# Sheet1.net
KiCad netlist of a schematic drawn in Altium Designer
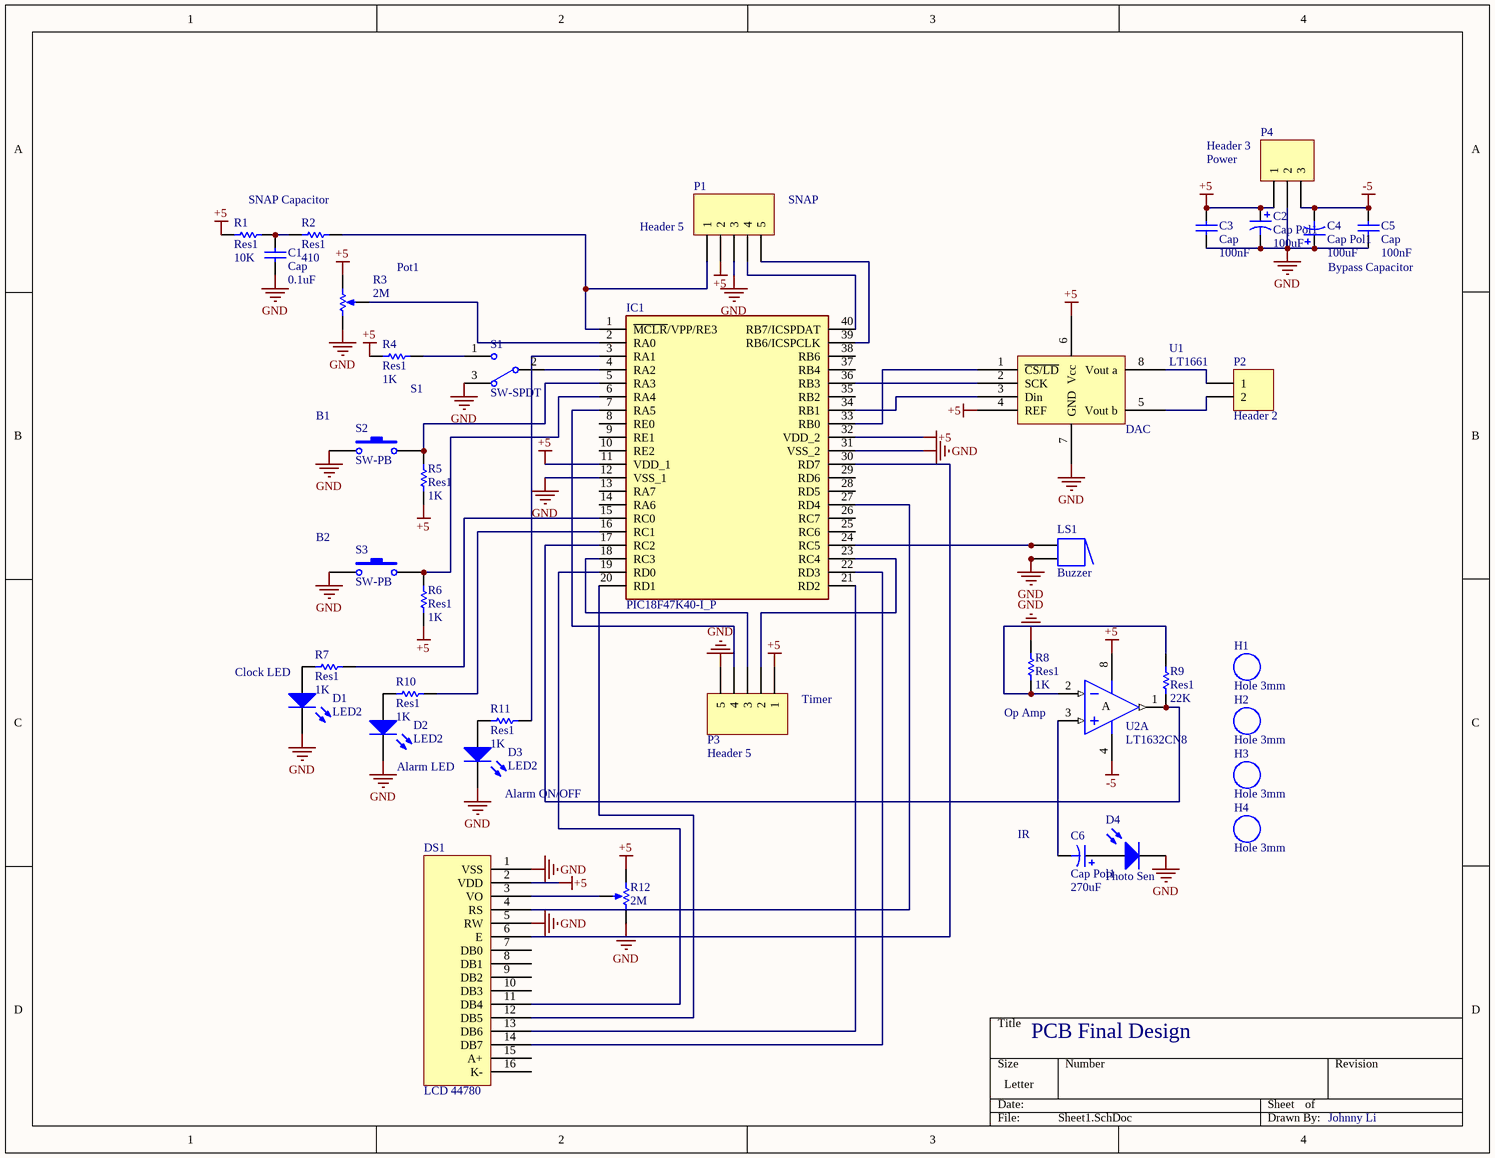
[diagram p0: Sheet1.SchDoc]

(export (version "E")
  (design (tool "Eeschema 10.0.6"))
  (components
    (comp (ref "C1")
      (value "Cap")
      (footprint "RAD-0.3")
      (description "Capacitor")
      (fields (field (name "ALTIUM_VALUE") "0.1uF") (field (name "PUBLISHER") "Altium Limited"))
      (libsource (lib "Miscellaneous Devices") (part "Cap"))
    )
    (comp (ref "C2")
      (value "Cap Pol1")
      (footprint "RAD-0.2")
      (description "Polarized Capacitor (Radial)")
      (fields (field (name "ALTIUM_VALUE") "100uF") (field (name "PUBLISHER") "Altium Limited"))
      (libsource (lib "Miscellaneous Devices") (part "Cap Pol1"))
    )
    (comp (ref "C3")
      (value "Cap")
      (footprint "RAD-0.3")
      (description "Capacitor")
      (fields (field (name "ALTIUM_VALUE") "100nF") (field (name "PUBLISHER") "Altium Limited"))
      (libsource (lib "Miscellaneous Devices") (part "Cap"))
    )
    (comp (ref "C4")
      (value "Cap Pol1")
      (footprint "RAD-0.2")
      (description "Polarized Capacitor (Radial)")
      (fields (field (name "ALTIUM_VALUE") "100uF") (field (name "PUBLISHER") "Altium Limited"))
      (libsource (lib "Miscellaneous Devices") (part "Cap Pol1"))
    )
    (comp (ref "C5")
      (value "Cap")
      (footprint "RAD-0.3")
      (description "Capacitor")
      (fields (field (name "ALTIUM_VALUE") "100nF") (field (name "PUBLISHER") "Altium Limited"))
      (libsource (lib "Miscellaneous Devices") (part "Cap"))
    )
    (comp (ref "C6")
      (value "Cap Pol1")
      (footprint "RAD-0.2")
      (description "Polarized Capacitor (Radial)")
      (fields (field (name "ALTIUM_VALUE") "270uF") (field (name "PUBLISHER") "Altium Limited"))
      (libsource (lib "Miscellaneous Devices") (part "Cap Pol1"))
    )
    (comp (ref "D1")
      (value "LED2")
      (footprint "3.2X1.6X1.1")
      (description "Typical RED, GREEN, YELLOW, AMBER GaAs LED")
      (fields (field (name "PUBLISHER") "Altium Limited"))
      (libsource (lib "Miscellaneous Devices") (part "LED2"))
    )
    (comp (ref "D2")
      (value "LED2")
      (footprint "3.2X1.6X1.1")
      (description "Typical RED, GREEN, YELLOW, AMBER GaAs LED")
      (fields (field (name "PUBLISHER") "Altium Limited"))
      (libsource (lib "Miscellaneous Devices") (part "LED2"))
    )
    (comp (ref "D3")
      (value "LED2")
      (footprint "3.2X1.6X1.1")
      (description "Typical RED, GREEN, YELLOW, AMBER GaAs LED")
      (fields (field (name "PUBLISHER") "Altium Limited"))
      (libsource (lib "Miscellaneous Devices") (part "LED2"))
    )
    (comp (ref "D4")
      (value "Photo Sen")
      (footprint "PIN2")
      (description "Photosensitive Diode")
      (fields (field (name "PUBLISHER") "Altium Limited"))
      (libsource (lib "Miscellaneous Devices") (part "Photo Sen"))
    )
    (comp (ref "DS1")
      (value "LCD 44780")
      (footprint "OLED 16x2")
      (libsource (lib "ECE LIB new") (part "LCD 44780"))
    )
    (comp (ref "H1")
      (value "Hole 3mm")
      (footprint "Hole 3mm")
      (libsource (lib "ECE LIB new") (part "Hole 3mm"))
    )
    (comp (ref "H2")
      (value "Hole 3mm")
      (footprint "Hole 3mm")
      (libsource (lib "ECE LIB new") (part "Hole 3mm"))
    )
    (comp (ref "H3")
      (value "Hole 3mm")
      (footprint "Hole 3mm")
      (libsource (lib "ECE LIB new") (part "Hole 3mm"))
    )
    (comp (ref "H4")
      (value "Hole 3mm")
      (footprint "Hole 3mm")
      (libsource (lib "ECE LIB new") (part "Hole 3mm"))
    )
    (comp (ref "IC1")
      (value "PIC18F47K40-I_P")
      (footprint "SamacSys:DIP1543W58P254L5175H635Q40N")
      (description "Integrated Circuit")
      (fields
        (field (name "MANUFACTURER_PART_NUMBER") "PIC18F47K40-I/P")
        (field (name "MOUSER PART NUMBER") "579-PIC18F47K40-I/P")
      )
      (libsource (lib "*") (part "PIC18F47K40-I_P"))
    )
    (comp (ref "LS1")
      (value "Buzzer")
      (footprint "ABSM-1574")
      (description "Magnetic Transducer Buzzer")
      (fields (field (name "PUBLISHER") "Altium Limited"))
      (libsource (lib "Miscellaneous Devices") (part "Buzzer"))
    )
    (comp (ref "P1")
      (value "Header 5")
      (footprint "HDR1X5")
      (description "Header, 5-Pin")
      (fields (field (name "PUBLISHER") "Altium Limited"))
      (libsource (lib "Miscellaneous Connectors") (part "Header 5"))
    )
    (comp (ref "P2")
      (value "Header 2")
      (footprint "HDR1X2")
      (description "Header, 2-Pin")
      (fields (field (name "PUBLISHER") "Altium Limited"))
      (libsource (lib "Miscellaneous Connectors") (part "Header 2"))
    )
    (comp (ref "P3")
      (value "Header 5")
      (footprint "HDR1X5")
      (description "Header, 5-Pin")
      (fields (field (name "PUBLISHER") "Altium Limited"))
      (libsource (lib "") (part "Header 5_1"))
    )
    (comp (ref "P4")
      (value "Header 3")
      (footprint "HDR1X3")
      (description "Header, 3-Pin")
      (fields (field (name "PUBLISHER") "Altium Limited"))
      (libsource (lib "Miscellaneous Connectors") (part "Header 3"))
    )
    (comp (ref "R1")
      (value "Res1")
      (footprint "AXIAL-0.3")
      (description "Resistor")
      (fields (field (name "ALTIUM_VALUE") "10K") (field (name "PUBLISHER") "Altium Limited"))
      (libsource (lib "Miscellaneous Devices") (part "Res1"))
    )
    (comp (ref "R2")
      (value "Res1")
      (footprint "AXIAL-0.3")
      (description "Resistor")
      (fields (field (name "ALTIUM_VALUE") "410") (field (name "PUBLISHER") "Altium Limited"))
      (libsource (lib "Miscellaneous Devices") (part "Res1"))
    )
    (comp (ref "R3")
      (value "2M")
      (footprint "CT2260-ND")
      (description "Potentiometer")
      (fields (field (name "Comment") "RPot_7") (field (name "PUBLISHER") "Altium Limited"))
      (libsource (lib "ECE LIB new") (part "RPot_4"))
    )
    (comp (ref "R4")
      (value "Res1")
      (footprint "AXIAL-0.3")
      (description "Resistor")
      (fields (field (name "ALTIUM_VALUE") "1K") (field (name "PUBLISHER") "Altium Limited"))
      (libsource (lib "Miscellaneous Devices") (part "Res1"))
    )
    (comp (ref "R5")
      (value "Res1")
      (footprint "AXIAL-0.3")
      (description "Resistor")
      (fields (field (name "ALTIUM_VALUE") "1K") (field (name "PUBLISHER") "Altium Limited"))
      (libsource (lib "Miscellaneous Devices") (part "Res1"))
    )
    (comp (ref "R6")
      (value "Res1")
      (footprint "AXIAL-0.3")
      (description "Resistor")
      (fields (field (name "ALTIUM_VALUE") "1K") (field (name "PUBLISHER") "Altium Limited"))
      (libsource (lib "Miscellaneous Devices") (part "Res1"))
    )
    (comp (ref "R7")
      (value "Res1")
      (footprint "AXIAL-0.3")
      (description "Resistor")
      (fields (field (name "ALTIUM_VALUE") "1K") (field (name "PUBLISHER") "Altium Limited"))
      (libsource (lib "Miscellaneous Devices") (part "Res1"))
    )
    (comp (ref "R8")
      (value "Res1")
      (footprint "AXIAL-0.3")
      (description "Resistor")
      (fields (field (name "ALTIUM_VALUE") "1K") (field (name "PUBLISHER") "Altium Limited"))
      (libsource (lib "Miscellaneous Devices") (part "Res1"))
    )
    (comp (ref "R9")
      (value "Res1")
      (footprint "AXIAL-0.3")
      (description "Resistor")
      (fields (field (name "ALTIUM_VALUE") "22K") (field (name "PUBLISHER") "Altium Limited"))
      (libsource (lib "Miscellaneous Devices") (part "Res1"))
    )
    (comp (ref "R10")
      (value "Res1")
      (footprint "AXIAL-0.3")
      (description "Resistor")
      (fields (field (name "ALTIUM_VALUE") "1K") (field (name "PUBLISHER") "Altium Limited"))
      (libsource (lib "Miscellaneous Devices") (part "Res1"))
    )
    (comp (ref "R11")
      (value "Res1")
      (footprint "AXIAL-0.3")
      (description "Resistor")
      (fields (field (name "ALTIUM_VALUE") "1K") (field (name "PUBLISHER") "Altium Limited"))
      (libsource (lib "Miscellaneous Devices") (part "Res1"))
    )
    (comp (ref "R12")
      (value "2M")
      (footprint "CT2260-ND")
      (description "Potentiometer")
      (fields (field (name "Comment") "RPot_7") (field (name "PUBLISHER") "Altium Limited"))
      (libsource (lib "ECE LIB new") (part "RPot_4"))
    )
    (comp (ref "S1")
      (value "SW-SPDT")
      (footprint "SW DPST jameco")
      (description "SPDT Subminiature Toggle Switch, Right Angle Mounting, Vertical Actuation")
      (fields (field (name "PUBLISHER") "Altium Limited"))
      (libsource (lib "Miscellaneous Devices") (part "SW-SPDT"))
    )
    (comp (ref "S2")
      (value "SW-PB")
      (footprint "SPST-2")
      (description "Switch")
      (fields (field (name "PUBLISHER") "Altium Limited"))
      (libsource (lib "Miscellaneous Devices") (part "SW-PB"))
    )
    (comp (ref "S3")
      (value "SW-PB")
      (footprint "SPST-2")
      (description "Switch")
      (fields (field (name "PUBLISHER") "Altium Limited"))
      (libsource (lib "Miscellaneous Devices") (part "SW-PB"))
    )
    (comp (ref "U1") (value "LT1661") (footprint "DIP-8") (libsource (lib "ECE LIB new") (part "LT1661")))
    (comp (ref "U2")
      (value "LT1632CN8")
      (footprint "SO08")
      (description "45MHz, 45V/µs, Dual Rail-to-Rail Input and Output Precision Operational Amplifier")
      (fields (field (name "PUBLISHER") "Altium Limited"))
      (libsource (lib "ECE LIB new") (part "LT1632CN8"))
    )
  )
  (nets
    (net (code "1") (name "+5") (class "Default")
      (node (ref "C2") (pin "1") (pinfunction "1_1") (pintype "passive"))
      (node (ref "C3") (pin "2") (pinfunction "2_2") (pintype "passive"))
      (node (ref "DS1") (pin "2") (pinfunction "VDD_2") (pintype "passive"))
      (node (ref "IC1") (pin "11") (pinfunction "VDD_1_11") (pintype "passive"))
      (node (ref "IC1") (pin "32") (pinfunction "VDD_2_32") (pintype "passive"))
      (node (ref "P1") (pin "2") (pinfunction "2_2") (pintype "passive"))
      (node (ref "P3") (pin "1") (pinfunction "1_1") (pintype "passive"))
      (node (ref "P4") (pin "1") (pinfunction "1_1") (pintype "passive"))
      (node (ref "R1") (pin "1") (pinfunction "1_1") (pintype "passive"))
      (node (ref "R12") (pin "1") (pinfunction "TOP_1") (pintype "passive"))
      (node (ref "R3") (pin "3") (pinfunction "BOT_3") (pintype "passive"))
      (node (ref "R4") (pin "1") (pinfunction "1_1") (pintype "passive"))
      (node (ref "R5") (pin "1") (pinfunction "1_1") (pintype "passive"))
      (node (ref "R6") (pin "1") (pinfunction "1_1") (pintype "passive"))
      (node (ref "U1") (pin "4") (pinfunction "REF_4") (pintype "passive"))
      (node (ref "U1") (pin "6") (pinfunction "Vcc_6") (pintype "passive"))
      (node (ref "U2") (pin "8") (pinfunction "V+_8") (pintype "power_in"))
    )
    (net (code "2") (name "-5") (class "Default")
      (node (ref "C4") (pin "2") (pinfunction "2_2") (pintype "passive"))
      (node (ref "C5") (pin "2") (pinfunction "2_2") (pintype "passive"))
      (node (ref "P4") (pin "3") (pinfunction "3_3") (pintype "passive"))
      (node (ref "U2") (pin "4") (pinfunction "V-_4") (pintype "power_in"))
    )
    (net (code "3") (name "GND") (class "Default")
      (node (ref "C1") (pin "1") (pinfunction "1_1") (pintype "passive"))
      (node (ref "C2") (pin "2") (pinfunction "2_2") (pintype "passive"))
      (node (ref "C3") (pin "1") (pinfunction "1_1") (pintype "passive"))
      (node (ref "C4") (pin "1") (pinfunction "1_1") (pintype "passive"))
      (node (ref "C5") (pin "1") (pinfunction "1_1") (pintype "passive"))
      (node (ref "D1") (pin "2") (pinfunction "K_2") (pintype "passive"))
      (node (ref "D2") (pin "2") (pinfunction "K_2") (pintype "passive"))
      (node (ref "D3") (pin "2") (pinfunction "K_2") (pintype "passive"))
      (node (ref "D4") (pin "2") (pinfunction "K_2") (pintype "passive"))
      (node (ref "DS1") (pin "1") (pinfunction "VSS_1") (pintype "passive"))
      (node (ref "DS1") (pin "5") (pinfunction "RW_5") (pintype "passive"))
      (node (ref "IC1") (pin "12") (pinfunction "VSS_1_12") (pintype "passive"))
      (node (ref "IC1") (pin "31") (pinfunction "VSS_2_31") (pintype "passive"))
      (node (ref "LS1") (pin "2") (pinfunction "2_2") (pintype "passive"))
      (node (ref "LS1") (pin "2A") (pinfunction "2A_2A") (pintype "passive"))
      (node (ref "P1") (pin "3") (pinfunction "3_3") (pintype "passive"))
      (node (ref "P3") (pin "5") (pinfunction "5_5") (pintype "passive"))
      (node (ref "P4") (pin "2") (pinfunction "2_2") (pintype "passive"))
      (node (ref "R12") (pin "3") (pinfunction "BOT_3") (pintype "passive"))
      (node (ref "R3") (pin "1") (pinfunction "TOP_1") (pintype "passive"))
      (node (ref "R8") (pin "2") (pinfunction "2_2") (pintype "passive"))
      (node (ref "S1") (pin "3") (pinfunction "3_3") (pintype "passive"))
      (node (ref "S2") (pin "1") (pinfunction "1_1") (pintype "passive"))
      (node (ref "S3") (pin "1") (pinfunction "1_1") (pintype "passive"))
      (node (ref "U1") (pin "7") (pinfunction "GND_7") (pintype "passive"))
    )
    (net (code "4") (name "Net-(C1-Pad2)") (class "Default")
      (node (ref "C1") (pin "2") (pinfunction "2_2") (pintype "passive"))
      (node (ref "R1") (pin "2") (pinfunction "2_2") (pintype "passive"))
      (node (ref "R2") (pin "1") (pinfunction "1_1") (pintype "passive"))
    )
    (net (code "5") (name "Net-(D1-A)") (class "Default")
      (node (ref "D1") (pin "1") (pinfunction "A_1") (pintype "passive"))
      (node (ref "R7") (pin "1") (pinfunction "1_1") (pintype "passive"))
    )
    (net (code "6") (name "Net-(D2-A)") (class "Default")
      (node (ref "D2") (pin "1") (pinfunction "A_1") (pintype "passive"))
      (node (ref "R10") (pin "1") (pinfunction "1_1") (pintype "passive"))
    )
    (net (code "7") (name "Net-(D3-A)") (class "Default")
      (node (ref "D3") (pin "1") (pinfunction "A_1") (pintype "passive"))
      (node (ref "R11") (pin "1") (pinfunction "1_1") (pintype "passive"))
    )
    (net (code "8") (name "Net-(D4-A)") (class "Default")
      (node (ref "C6") (pin "1") (pinfunction "1_1") (pintype "passive"))
      (node (ref "D4") (pin "1") (pinfunction "A_1") (pintype "passive"))
    )
    (net (code "9") (name "Net-(DS1-DB4)") (class "Default")
      (node (ref "DS1") (pin "11") (pinfunction "DB4_11") (pintype "passive"))
      (node (ref "IC1") (pin "19") (pinfunction "RD0_19") (pintype "passive"))
    )
    (net (code "10") (name "Net-(DS1-DB5)") (class "Default")
      (node (ref "DS1") (pin "12") (pinfunction "DB5_12") (pintype "passive"))
      (node (ref "IC1") (pin "20") (pinfunction "RD1_20") (pintype "passive"))
    )
    (net (code "11") (name "Net-(DS1-DB6)") (class "Default")
      (node (ref "DS1") (pin "13") (pinfunction "DB6_13") (pintype "passive"))
      (node (ref "IC1") (pin "21") (pinfunction "RD2_21") (pintype "passive"))
    )
    (net (code "12") (name "Net-(DS1-DB7)") (class "Default")
      (node (ref "DS1") (pin "14") (pinfunction "DB7_14") (pintype "passive"))
      (node (ref "IC1") (pin "22") (pinfunction "RD3_22") (pintype "passive"))
    )
    (net (code "13") (name "Net-(DS1-E)") (class "Default")
      (node (ref "DS1") (pin "6") (pinfunction "E_6") (pintype "passive"))
      (node (ref "IC1") (pin "30") (pinfunction "RD7_30") (pintype "passive"))
    )
    (net (code "14") (name "Net-(DS1-RS)") (class "Default")
      (node (ref "DS1") (pin "4") (pinfunction "RS_4") (pintype "passive"))
      (node (ref "IC1") (pin "27") (pinfunction "RD4_27") (pintype "passive"))
    )
    (net (code "15") (name "Net-(DS1-VO)") (class "Default")
      (node (ref "DS1") (pin "3") (pinfunction "VO_3") (pintype "passive"))
      (node (ref "R12") (pin "2") (pinfunction "TAP_2") (pintype "passive"))
    )
    (net (code "16") (name "Net-(IC1-RA0)") (class "Default")
      (node (ref "IC1") (pin "2") (pinfunction "RA0_2") (pintype "passive"))
      (node (ref "R3") (pin "2") (pinfunction "TAP_2") (pintype "passive"))
    )
    (net (code "17") (name "Net-(IC1-RA1)") (class "Default")
      (node (ref "IC1") (pin "3") (pinfunction "RA1_3") (pintype "passive"))
      (node (ref "R11") (pin "2") (pinfunction "2_2") (pintype "passive"))
    )
    (net (code "18") (name "Net-(IC1-RA2)") (class "Default")
      (node (ref "IC1") (pin "4") (pinfunction "RA2_4") (pintype "passive"))
      (node (ref "S1") (pin "2") (pinfunction "2_2") (pintype "passive"))
    )
    (net (code "19") (name "Net-(IC1-RA3)") (class "Default")
      (node (ref "IC1") (pin "5") (pinfunction "RA3_5") (pintype "passive"))
      (node (ref "R5") (pin "2") (pinfunction "2_2") (pintype "passive"))
      (node (ref "S2") (pin "2") (pinfunction "2_2") (pintype "passive"))
    )
    (net (code "20") (name "Net-(IC1-RA4)") (class "Default")
      (node (ref "IC1") (pin "6") (pinfunction "RA4_6") (pintype "passive"))
      (node (ref "R6") (pin "2") (pinfunction "2_2") (pintype "passive"))
      (node (ref "S3") (pin "2") (pinfunction "2_2") (pintype "passive"))
    )
    (net (code "21") (name "Net-(IC1-RA5)") (class "Default")
      (node (ref "IC1") (pin "7") (pinfunction "RA5_7") (pintype "passive"))
      (node (ref "P3") (pin "4") (pinfunction "4_4") (pintype "passive"))
    )
    (net (code "22") (name "Net-(IC1-RB0)") (class "Default")
      (node (ref "IC1") (pin "33") (pinfunction "RB0_33") (pintype "passive"))
      (node (ref "U1") (pin "1") (pinfunction "~{CS/LD}_1") (pintype "passive"))
    )
    (net (code "23") (name "Net-(IC1-RB1)") (class "Default")
      (node (ref "IC1") (pin "34") (pinfunction "RB1_34") (pintype "passive"))
      (node (ref "U1") (pin "3") (pinfunction "Din_3") (pintype "passive"))
    )
    (net (code "24") (name "Net-(IC1-RB3)") (class "Default")
      (node (ref "IC1") (pin "36") (pinfunction "RB3_36") (pintype "passive"))
      (node (ref "U1") (pin "2") (pinfunction "SCK_2") (pintype "passive"))
    )
    (net (code "25") (name "Net-(IC1-RB6{slash}ICSPCLK)") (class "Default")
      (node (ref "IC1") (pin "39") (pinfunction "RB6/ICSPCLK_39") (pintype "passive"))
      (node (ref "P1") (pin "5") (pinfunction "5_5") (pintype "passive"))
    )
    (net (code "26") (name "Net-(IC1-RB7{slash}ICSPDAT)") (class "Default")
      (node (ref "IC1") (pin "40") (pinfunction "RB7/ICSPDAT_40") (pintype "passive"))
      (node (ref "P1") (pin "4") (pinfunction "4_4") (pintype "passive"))
    )
    (net (code "27") (name "Net-(IC1-RC0)") (class "Default")
      (node (ref "IC1") (pin "15") (pinfunction "RC0_15") (pintype "passive"))
      (node (ref "R7") (pin "2") (pinfunction "2_2") (pintype "passive"))
    )
    (net (code "28") (name "Net-(IC1-RC1)") (class "Default")
      (node (ref "IC1") (pin "16") (pinfunction "RC1_16") (pintype "passive"))
      (node (ref "R10") (pin "2") (pinfunction "2_2") (pintype "passive"))
    )
    (net (code "29") (name "Net-(IC1-RC2)") (class "Default")
      (node (ref "IC1") (pin "17") (pinfunction "RC2_17") (pintype "passive"))
      (node (ref "R9") (pin "1") (pinfunction "1_1") (pintype "passive"))
      (node (ref "U2") (pin "1") (pinfunction "OUT_1") (pintype "output"))
    )
    (net (code "30") (name "Net-(IC1-RC3)") (class "Default")
      (node (ref "IC1") (pin "18") (pinfunction "RC3_18") (pintype "passive"))
      (node (ref "P3") (pin "3") (pinfunction "3_3") (pintype "passive"))
    )
    (net (code "31") (name "Net-(IC1-RC4)") (class "Default")
      (node (ref "IC1") (pin "23") (pinfunction "RC4_23") (pintype "passive"))
      (node (ref "P3") (pin "2") (pinfunction "2_2") (pintype "passive"))
    )
    (net (code "32") (name "Net-(IC1-RC5)") (class "Default")
      (node (ref "IC1") (pin "24") (pinfunction "RC5_24") (pintype "passive"))
      (node (ref "LS1") (pin "1") (pinfunction "1_1") (pintype "passive"))
      (node (ref "LS1") (pin "1A") (pinfunction "1A_1A") (pintype "passive"))
    )
    (net (code "33") (name "Net-(IC1-~{MCLR}{slash}VPP{slash}RE3)") (class "Default")
      (node (ref "IC1") (pin "1") (pinfunction "~{MCLR}/VPP/RE3_1") (pintype "passive"))
      (node (ref "P1") (pin "1") (pinfunction "1_1") (pintype "passive"))
      (node (ref "R2") (pin "2") (pinfunction "2_2") (pintype "passive"))
    )
    (net (code "34") (name "Net-(R4-Pad2)") (class "Default")
      (node (ref "R4") (pin "2") (pinfunction "2_2") (pintype "passive"))
      (node (ref "S1") (pin "1") (pinfunction "1_1") (pintype "passive"))
    )
    (net (code "35") (name "Net-(U1-Vout_a)") (class "Default")
      (node (ref "P2") (pin "1") (pinfunction "1_1") (pintype "passive"))
      (node (ref "U1") (pin "8") (pinfunction "Vout_a_8") (pintype "passive"))
    )
    (net (code "36") (name "Net-(U1-Vout_b)") (class "Default")
      (node (ref "P2") (pin "2") (pinfunction "2_2") (pintype "passive"))
      (node (ref "U1") (pin "5") (pinfunction "Vout_b_5") (pintype "passive"))
    )
    (net (code "37") (name "Net-(U2A-IN+)") (class "Default")
      (node (ref "C6") (pin "2") (pinfunction "2_2") (pintype "passive"))
      (node (ref "U2") (pin "3") (pinfunction "IN+_3") (pintype "input"))
    )
    (net (code "38") (name "Net-(U2A-IN-)") (class "Default")
      (node (ref "R8") (pin "1") (pinfunction "1_1") (pintype "passive"))
      (node (ref "R9") (pin "2") (pinfunction "2_2") (pintype "passive"))
      (node (ref "U2") (pin "2") (pinfunction "IN-_2") (pintype "input"))
    )
    (net (code "39") (name "unconnected-(DS1-A+-Pad15)") (class "Default")
      (node (ref "DS1") (pin "15") (pinfunction "A+_15") (pintype "passive"))
    )
    (net (code "40") (name "unconnected-(DS1-DB0-Pad7)") (class "Default")
      (node (ref "DS1") (pin "7") (pinfunction "DB0_7") (pintype "passive"))
    )
    (net (code "41") (name "unconnected-(DS1-DB1-Pad8)") (class "Default")
      (node (ref "DS1") (pin "8") (pinfunction "DB1_8") (pintype "passive"))
    )
    (net (code "42") (name "unconnected-(DS1-DB2-Pad9)") (class "Default")
      (node (ref "DS1") (pin "9") (pinfunction "DB2_9") (pintype "passive"))
    )
    (net (code "43") (name "unconnected-(DS1-DB3-Pad10)") (class "Default")
      (node (ref "DS1") (pin "10") (pinfunction "DB3_10") (pintype "passive"))
    )
    (net (code "44") (name "unconnected-(DS1-K--Pad16)") (class "Default")
      (node (ref "DS1") (pin "16") (pinfunction "K-_16") (pintype "passive"))
    )
    (net (code "45") (name "unconnected-(IC1-RA6-Pad14)") (class "Default")
      (node (ref "IC1") (pin "14") (pinfunction "RA6_14") (pintype "passive"))
    )
    (net (code "46") (name "unconnected-(IC1-RA7-Pad13)") (class "Default")
      (node (ref "IC1") (pin "13") (pinfunction "RA7_13") (pintype "passive"))
    )
    (net (code "47") (name "unconnected-(IC1-RB2-Pad35)") (class "Default")
      (node (ref "IC1") (pin "35") (pinfunction "RB2_35") (pintype "passive"))
    )
    (net (code "48") (name "unconnected-(IC1-RB4-Pad37)") (class "Default")
      (node (ref "IC1") (pin "37") (pinfunction "RB4_37") (pintype "passive"))
    )
    (net (code "49") (name "unconnected-(IC1-RB6-Pad38)") (class "Default")
      (node (ref "IC1") (pin "38") (pinfunction "RB6_38") (pintype "passive"))
    )
    (net (code "50") (name "unconnected-(IC1-RC6-Pad25)") (class "Default")
      (node (ref "IC1") (pin "25") (pinfunction "RC6_25") (pintype "passive"))
    )
    (net (code "51") (name "unconnected-(IC1-RC7-Pad26)") (class "Default")
      (node (ref "IC1") (pin "26") (pinfunction "RC7_26") (pintype "passive"))
    )
    (net (code "52") (name "unconnected-(IC1-RD5-Pad28)") (class "Default")
      (node (ref "IC1") (pin "28") (pinfunction "RD5_28") (pintype "passive"))
    )
    (net (code "53") (name "unconnected-(IC1-RD6-Pad29)") (class "Default")
      (node (ref "IC1") (pin "29") (pinfunction "RD6_29") (pintype "passive"))
    )
    (net (code "54") (name "unconnected-(IC1-RE0-Pad8)") (class "Default")
      (node (ref "IC1") (pin "8") (pinfunction "RE0_8") (pintype "passive"))
    )
    (net (code "55") (name "unconnected-(IC1-RE1-Pad9)") (class "Default")
      (node (ref "IC1") (pin "9") (pinfunction "RE1_9") (pintype "passive"))
    )
    (net (code "56") (name "unconnected-(IC1-RE2-Pad10)") (class "Default")
      (node (ref "IC1") (pin "10") (pinfunction "RE2_10") (pintype "passive"))
    )
  )
)
